# AudioAmplifier.net
KiCad netlist of a schematic drawn in Altium Designer
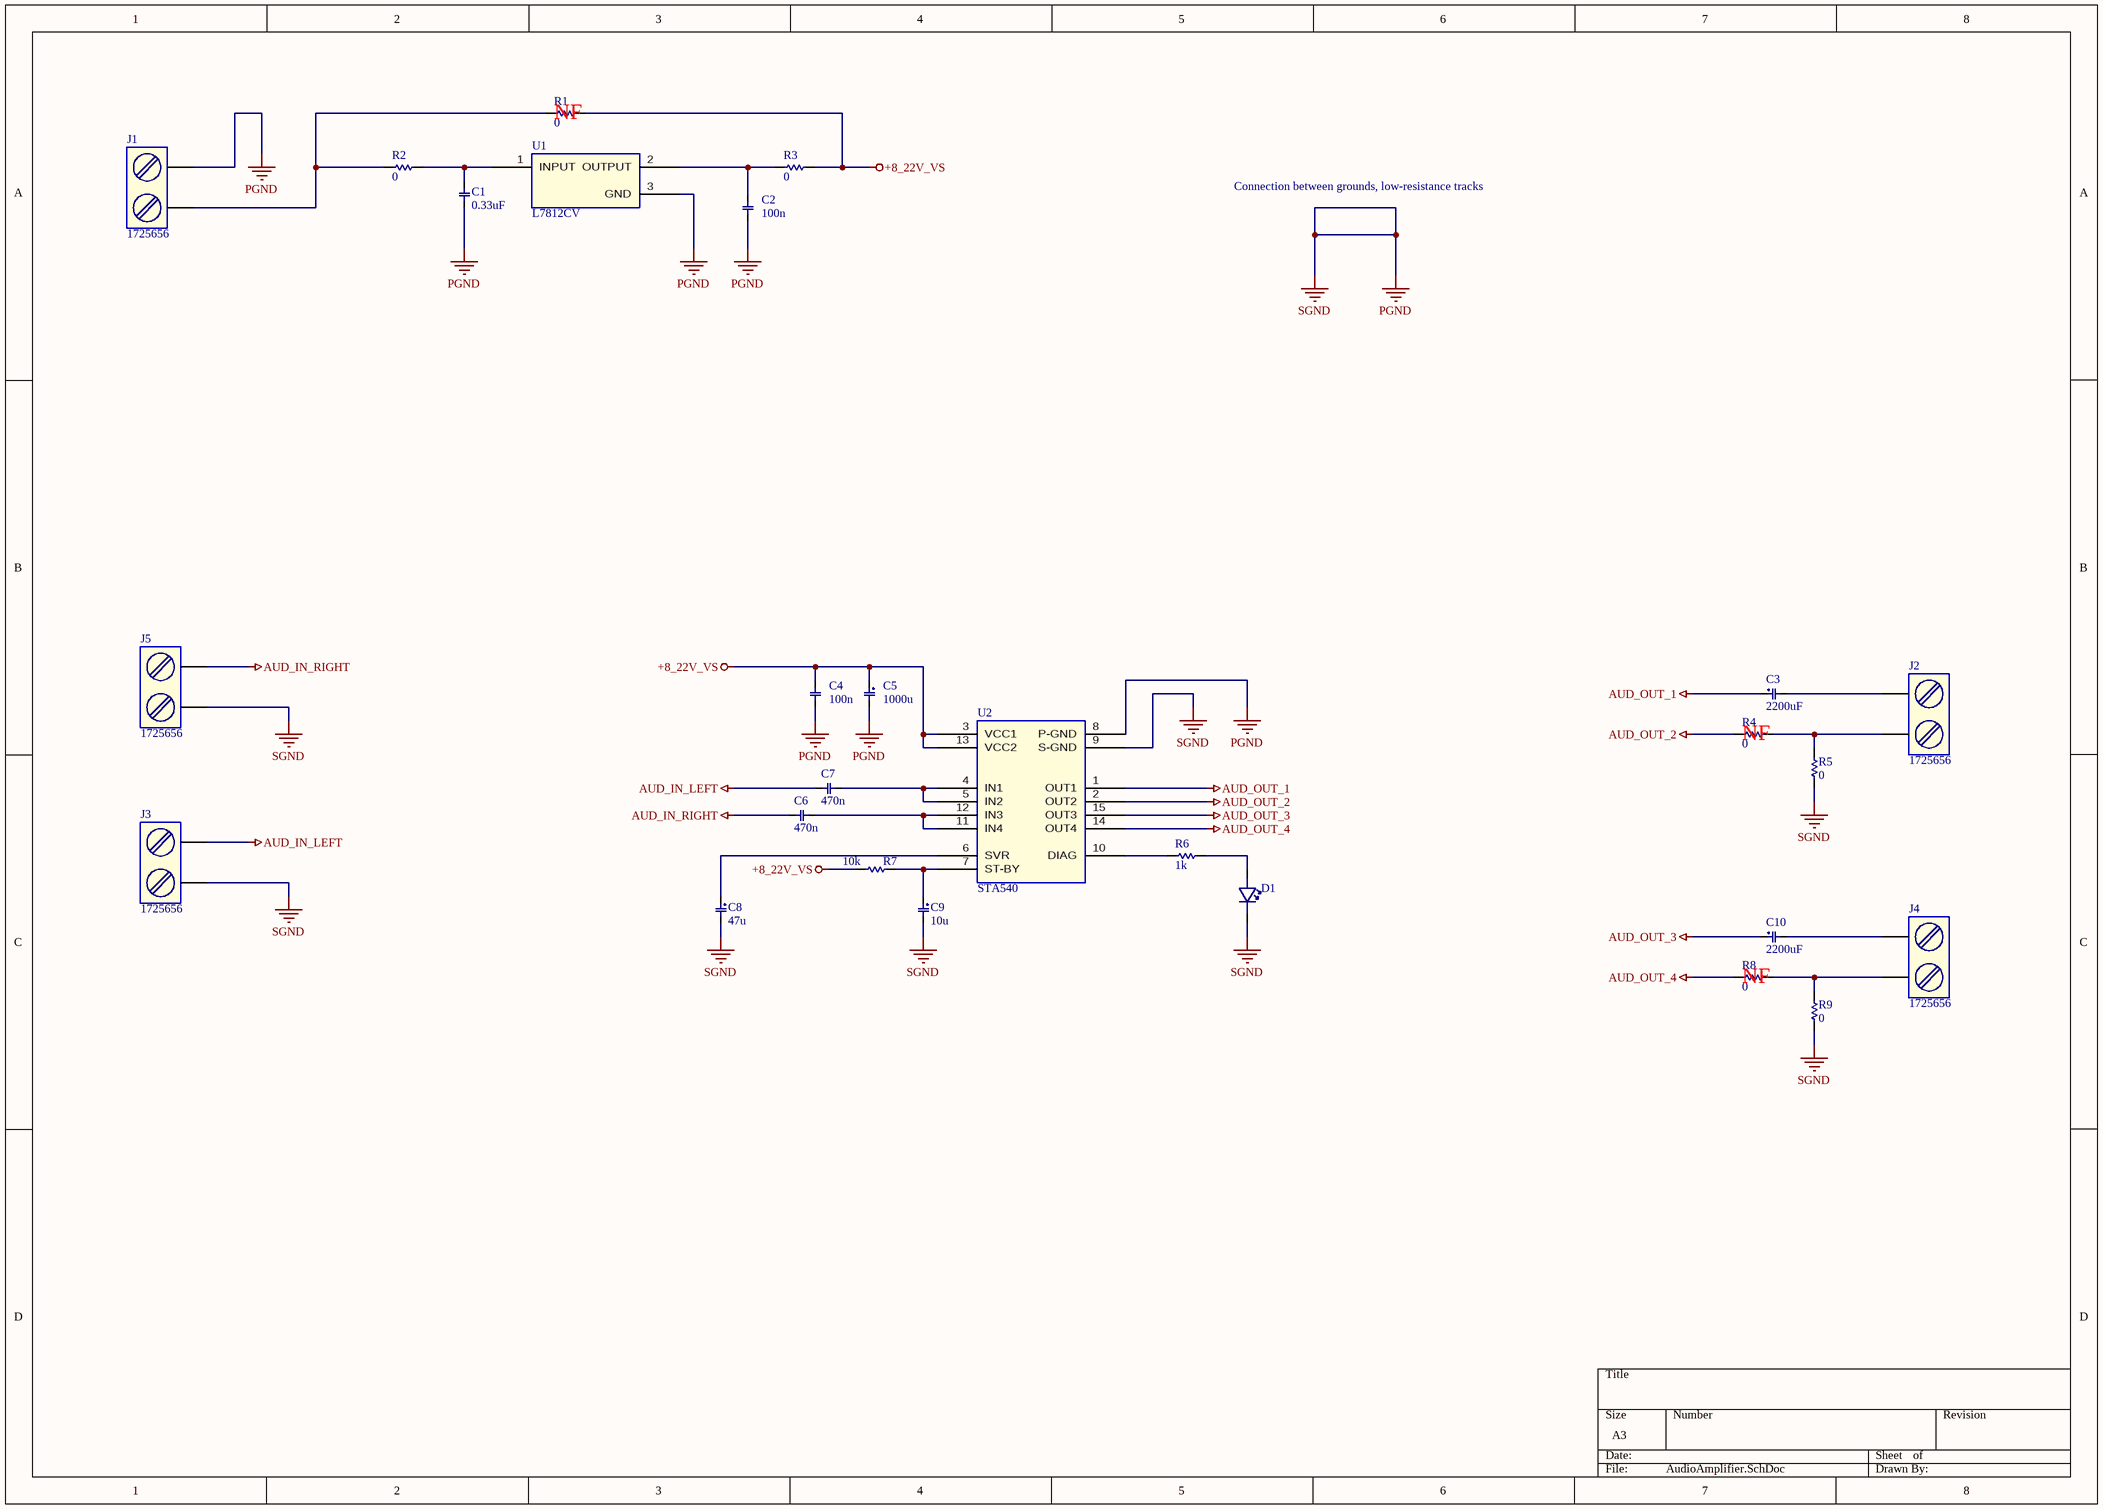
[diagram p0: AudioAmplifier.SchDoc]

(export (version "E")
  (design (tool "Eeschema 10.0.6"))
  (components
    (comp (ref "C1")
      (value "0.33uF")
      (footprint "CERAMIC CAPACITOR")
      (description "Multilayer Ceramic Capacitors MLCC - Leaded 50volts .33uF 20%")
      (fields (field (name "MANUFACTURER") "AVX") (field (name "MANUFACTURER PART NUMBER") "SR215E334MARTR2"))
      (libsource (lib "AudioAmplifier") (part "SR215E334MARTR2"))
    )
    (comp (ref "C2")
      (value "100n")
      (footprint "CERAMIC CAPACITOR")
      (description "Multilayer Ceramic Capacitors MLCC - Leaded .1uF 50volts 10% 5.0mm X7R")
      (fields
        (field (name "MANUFACTURER") "Vishay / BC Components")
        (field (name "MANUFACTURER PART NUMBER") "K104K15X7RF5UH5")
      )
      (libsource (lib "AudioAmplifier") (part "K104K15X7RF5UH5"))
    )
    (comp (ref "C3")
      (value "2200uF")
      (footprint "ELECTROLYTIC_CAPACITOR")
      (description "Aluminium Electrolytic Capacitors - Leaded 50volts 2200uF 16x31.5 20% 7.5LS")
      (fields
        (field (name "MANUFACTURER") "Nichicon")
        (field (name "MANUFACTURER PART NUMBER") "UVK1H222MHD")
      )
      (libsource (lib "AudioAmplifier") (part "UVK1H222MHD"))
    )
    (comp (ref "C4")
      (value "100n")
      (footprint "CERAMIC CAPACITOR")
      (description "Multilayer Ceramic Capacitors MLCC - Leaded .1uF 50volts 10% 5.0mm X7R")
      (fields
        (field (name "MANUFACTURER") "Vishay / BC Components")
        (field (name "MANUFACTURER PART NUMBER") "K104K15X7RF5UH5")
      )
      (libsource (lib "AudioAmplifier") (part "K104K15X7RF5UH5"))
    )
    (comp (ref "C5")
      (value "1000u")
      (footprint "ELECTROLYTIC_CAPACITOR")
      (description "Aluminium Electrolytic Capacitors - Leaded 1000uF 25V 85c")
      (fields
        (field (name "MANUFACTURER") "Nichicon")
        (field (name "MANUFACTURER PART NUMBER") "UVR1E102MPD1TD")
      )
      (libsource (lib "AudioAmplifier") (part "UVR1E102MPD1TD"))
    )
    (comp (ref "C6")
      (value "470n")
      (footprint "CERAMIC CAPACITOR")
      (description "Multilayer Ceramic Capacitors MLCC - Leaded 0.47uF 25volts X5R +/-10%")
      (fields (field (name "MANUFACTURER") "TDK") (field (name "MANUFACTURER PART NUMBER") "FK28X5R1E474K"))
      (libsource (lib "AudioAmplifier") (part "FK28X5R1E474K"))
    )
    (comp (ref "C7")
      (value "470n")
      (footprint "CERAMIC CAPACITOR")
      (description "Multilayer Ceramic Capacitors MLCC - Leaded 0.47uF 25volts X5R +/-10%")
      (fields (field (name "MANUFACTURER") "TDK") (field (name "MANUFACTURER PART NUMBER") "FK28X5R1E474K"))
      (libsource (lib "AudioAmplifier") (part "FK28X5R1E474K"))
    )
    (comp (ref "C8")
      (value "47u")
      (footprint "ELECTROLYTIC_CAPACITOR")
      (description "Aluminium Electrolytic Capacitors - Leaded 35V 47uF 105C 6.3x11mm")
      (fields
        (field (name "MANUFACTURER") "Lelon")
        (field (name "MANUFACTURER PART NUMBER") "RGA470M1VBK-0611G")
      )
      (libsource (lib "AudioAmplifier") (part "RGA470M1VBK-0611G"))
    )
    (comp (ref "C9")
      (value "10u")
      (footprint "ELECTROLYTIC_CAPACITOR")
      (description "Aluminium Electrolytic Capacitors - Leaded 50V 10uF 20% 5x11mm")
      (fields
        (field (name "MANUFACTURER") "Lelon")
        (field (name "MANUFACTURER PART NUMBER") "REA100M1HBK-0511P")
      )
      (libsource (lib "AudioAmplifier") (part "REA100M1HBK-0511P"))
    )
    (comp (ref "C10")
      (value "2200uF")
      (footprint "ELECTROLYTIC_CAPACITOR")
      (description "Aluminium Electrolytic Capacitors - Leaded 50volts 2200uF 16x31.5 20% 7.5LS")
      (fields
        (field (name "MANUFACTURER") "Nichicon")
        (field (name "MANUFACTURER PART NUMBER") "UVK1H222MHD")
      )
      (libsource (lib "AudioAmplifier") (part "UVK1H222MHD"))
    )
    (comp (ref "D1")
      (value "350-00006")
      (footprint "LED")
      (description "Standard LEDs - Through Hole Red LED")
      (fields (field (name "MANUFACTURER") "Parallax"))
      (libsource (lib "AudioAmplifier") (part "350-00006"))
    )
    (comp (ref "J1")
      (value "1725656")
      (footprint "1725656")
      (description "Fixed Terminal Blocks 2P 2.54mm 90DEG")
      (fields (field (name "MANUFACTURER") "Phoenix Contact"))
      (libsource (lib "") (part "1725656_1"))
    )
    (comp (ref "J2")
      (value "1725656")
      (footprint "1725656")
      (description "Fixed Terminal Blocks 2P 2.54mm 90DEG")
      (fields (field (name "MANUFACTURER") "Phoenix Contact"))
      (libsource (lib "AudioAmplifier") (part "1725656"))
    )
    (comp (ref "J3")
      (value "1725656")
      (footprint "1725656")
      (description "Fixed Terminal Blocks 2P 2.54mm 90DEG")
      (fields (field (name "MANUFACTURER") "Phoenix Contact"))
      (libsource (lib "") (part "1725656_1"))
    )
    (comp (ref "J4")
      (value "1725656")
      (footprint "1725656")
      (description "Fixed Terminal Blocks 2P 2.54mm 90DEG")
      (fields (field (name "MANUFACTURER") "Phoenix Contact"))
      (libsource (lib "AudioAmplifier") (part "1725656"))
    )
    (comp (ref "J5")
      (value "1725656")
      (footprint "1725656")
      (description "Fixed Terminal Blocks 2P 2.54mm 90DEG")
      (fields (field (name "MANUFACTURER") "Phoenix Contact"))
      (libsource (lib "") (part "1725656_1"))
    )
    (comp (ref "R1")
      (value "0")
      (footprint "Resistor")
      (description "Metal Film Resistors - Through Hole 400mW 0 Ohm Jumper SFR55 Historical p/n")
      (fields
        (field (name "MANUFACTURER") "Vishay / BC Components")
        (field (name "MANUFACTURER PART NUMBER") "SFR25000Z0000ZR500")
      )
      (libsource (lib "AudioAmplifier") (part "SFR25000Z0000ZR500"))
    )
    (comp (ref "R2")
      (value "0")
      (footprint "Resistor")
      (description "Metal Film Resistors - Through Hole 400mW 0 Ohm Jumper SFR55 Historical p/n")
      (fields
        (field (name "MANUFACTURER") "Vishay / BC Components")
        (field (name "MANUFACTURER PART NUMBER") "SFR25000Z0000ZR500")
      )
      (libsource (lib "AudioAmplifier") (part "SFR25000Z0000ZR500"))
    )
    (comp (ref "R3")
      (value "0")
      (footprint "Resistor")
      (description "Metal Film Resistors - Through Hole 400mW 0 Ohm Jumper SFR55 Historical p/n")
      (fields
        (field (name "MANUFACTURER") "Vishay / BC Components")
        (field (name "MANUFACTURER PART NUMBER") "SFR25000Z0000ZR500")
      )
      (libsource (lib "AudioAmplifier") (part "SFR25000Z0000ZR500"))
    )
    (comp (ref "R4")
      (value "0")
      (footprint "Resistor")
      (description "Metal Film Resistors - Through Hole 400mW 0 Ohm Jumper SFR55 Historical p/n")
      (fields
        (field (name "MANUFACTURER") "Vishay / BC Components")
        (field (name "MANUFACTURER PART NUMBER") "SFR25000Z0000ZR500")
      )
      (libsource (lib "AudioAmplifier") (part "SFR25000Z0000ZR500"))
    )
    (comp (ref "R5")
      (value "0")
      (footprint "Resistor")
      (description "Metal Film Resistors - Through Hole 400mW 0 Ohm Jumper SFR55 Historical p/n")
      (fields
        (field (name "MANUFACTURER") "Vishay / BC Components")
        (field (name "MANUFACTURER PART NUMBER") "SFR25000Z0000ZR500")
      )
      (libsource (lib "AudioAmplifier") (part "SFR25000Z0000ZR500"))
    )
    (comp (ref "R6")
      (value "1k")
      (footprint "Resistor")
      (description "Metal Film Resistors - Through Hole 1/2W1K ohm 1%")
      (fields
        (field (name "MANUFACTURER") "KOA Speer")
        (field (name "MANUFACTURER PART NUMBER") "MFS1/2DCT52R1001F")
      )
      (libsource (lib "AudioAmplifier") (part "MFS1/2DCT52R1001F"))
    )
    (comp (ref "R7")
      (value "10k")
      (footprint "Resistor")
      (description "Metal Film Resistors - Through Hole 1/2watt 10Kohms 1%")
      (fields
        (field (name "MANUFACTURER") "Vishay / BC Components")
        (field (name "MANUFACTURER PART NUMBER") "SFR16S0001002FR500")
      )
      (libsource (lib "AudioAmplifier") (part "SFR16S0001002FR500"))
    )
    (comp (ref "R8")
      (value "0")
      (footprint "Resistor")
      (description "Metal Film Resistors - Through Hole 400mW 0 Ohm Jumper SFR55 Historical p/n")
      (fields
        (field (name "MANUFACTURER") "Vishay / BC Components")
        (field (name "MANUFACTURER PART NUMBER") "SFR25000Z0000ZR500")
      )
      (libsource (lib "AudioAmplifier") (part "SFR25000Z0000ZR500"))
    )
    (comp (ref "R9")
      (value "0")
      (footprint "Resistor")
      (description "Metal Film Resistors - Through Hole 400mW 0 Ohm Jumper SFR55 Historical p/n")
      (fields
        (field (name "MANUFACTURER") "Vishay / BC Components")
        (field (name "MANUFACTURER PART NUMBER") "SFR25000Z0000ZR500")
      )
      (libsource (lib "AudioAmplifier") (part "SFR25000Z0000ZR500"))
    )
    (comp (ref "U1")
      (value "L7812CV")
      (footprint "TO-220")
      (description "Linear Voltage Regulators 12V 1.5A Positive")
      (fields (field (name "MANUFACTURER") "STMicroelectronics"))
      (libsource (lib "AudioAmplifier") (part "L7812CV"))
    )
    (comp (ref "U2")
      (value "STA540")
      (footprint "Multiwatt15")
      (description "Audio Amplifiers 4-CH AB Audio AMP 4 X 13 W Dual/Quad")
      (fields (field (name "MANUFACTURER") "STMicroelectronics"))
      (libsource (lib "AudioAmplifier") (part "STA540"))
    )
  )
  (nets
    (net (code "1") (name "+8_22V_VS") (class "Default")
      (node (ref "C4") (pin "1") (pinfunction "1_1") (pintype "passive"))
      (node (ref "C5") (pin "1") (pinfunction "1_1") (pintype "passive"))
      (node (ref "R1") (pin "2") (pinfunction "2_2") (pintype "passive"))
      (node (ref "R3") (pin "2") (pinfunction "2_2") (pintype "passive"))
      (node (ref "R7") (pin "1") (pinfunction "1_1") (pintype "passive"))
      (node (ref "U2") (pin "13") (pinfunction "VCC2_13") (pintype "passive"))
      (node (ref "U2") (pin "3") (pinfunction "VCC1_3") (pintype "passive"))
    )
    (net (code "2") (name "AUD_IN_LEFT") (class "Default")
      (node (ref "C7") (pin "1") (pinfunction "1_1") (pintype "passive"))
      (node (ref "J3") (pin "2") (pinfunction "2_2") (pintype "passive"))
    )
    (net (code "3") (name "AUD_IN_RIGHT") (class "Default")
      (node (ref "C6") (pin "1") (pinfunction "1_1") (pintype "passive"))
      (node (ref "J5") (pin "2") (pinfunction "2_2") (pintype "passive"))
    )
    (net (code "4") (name "AUD_OUT_1") (class "Default")
      (node (ref "C3") (pin "1") (pinfunction "1_1") (pintype "passive"))
      (node (ref "U2") (pin "1") (pinfunction "OUT1_1") (pintype "passive"))
    )
    (net (code "5") (name "AUD_OUT_2") (class "Default")
      (node (ref "R4") (pin "1") (pinfunction "1_1") (pintype "passive"))
      (node (ref "U2") (pin "2") (pinfunction "OUT2_2") (pintype "passive"))
    )
    (net (code "6") (name "AUD_OUT_3") (class "Default")
      (node (ref "C10") (pin "1") (pinfunction "1_1") (pintype "passive"))
      (node (ref "U2") (pin "15") (pinfunction "OUT3_15") (pintype "passive"))
    )
    (net (code "7") (name "AUD_OUT_4") (class "Default")
      (node (ref "R8") (pin "1") (pinfunction "1_1") (pintype "passive"))
      (node (ref "U2") (pin "14") (pinfunction "OUT4_14") (pintype "passive"))
    )
    (net (code "8") (name "Net-(C3-Pad2)") (class "Default")
      (node (ref "C3") (pin "2") (pinfunction "2_2") (pintype "passive"))
      (node (ref "J2") (pin "1") (pinfunction "1_1") (pintype "passive"))
    )
    (net (code "9") (name "Net-(C10-Pad2)") (class "Default")
      (node (ref "C10") (pin "2") (pinfunction "2_2") (pintype "passive"))
      (node (ref "J4") (pin "1") (pinfunction "1_1") (pintype "passive"))
    )
    (net (code "10") (name "Net-(D1-Pad1)") (class "Default")
      (node (ref "D1") (pin "1") (pinfunction "1_1") (pintype "passive"))
      (node (ref "R6") (pin "1") (pinfunction "1_1") (pintype "passive"))
    )
    (net (code "11") (name "Net-(J1-Pad1)") (class "Default")
      (node (ref "J1") (pin "1") (pinfunction "1_1") (pintype "passive"))
      (node (ref "R1") (pin "1") (pinfunction "1_1") (pintype "passive"))
      (node (ref "R2") (pin "1") (pinfunction "1_1") (pintype "passive"))
    )
    (net (code "12") (name "Net-(J2-Pad2)") (class "Default")
      (node (ref "J2") (pin "2") (pinfunction "2_2") (pintype "passive"))
      (node (ref "R4") (pin "2") (pinfunction "2_2") (pintype "passive"))
      (node (ref "R5") (pin "2") (pinfunction "2_2") (pintype "passive"))
    )
    (net (code "13") (name "Net-(J4-Pad2)") (class "Default")
      (node (ref "J4") (pin "2") (pinfunction "2_2") (pintype "passive"))
      (node (ref "R8") (pin "2") (pinfunction "2_2") (pintype "passive"))
      (node (ref "R9") (pin "2") (pinfunction "2_2") (pintype "passive"))
    )
    (net (code "14") (name "Net-(U1-INPUT)") (class "Default")
      (node (ref "C1") (pin "2") (pinfunction "2_2") (pintype "passive"))
      (node (ref "R2") (pin "2") (pinfunction "2_2") (pintype "passive"))
      (node (ref "U1") (pin "1") (pinfunction "INPUT_1") (pintype "passive"))
    )
    (net (code "15") (name "Net-(U1-OUTPUT)") (class "Default")
      (node (ref "C2") (pin "1") (pinfunction "1_1") (pintype "passive"))
      (node (ref "R3") (pin "1") (pinfunction "1_1") (pintype "passive"))
      (node (ref "U1") (pin "2") (pinfunction "OUTPUT_2") (pintype "passive"))
    )
    (net (code "16") (name "Net-(U2-DIAG)") (class "Default")
      (node (ref "R6") (pin "2") (pinfunction "2_2") (pintype "passive"))
      (node (ref "U2") (pin "10") (pinfunction "DIAG_10") (pintype "passive"))
    )
    (net (code "17") (name "Net-(U2-IN1)") (class "Default")
      (node (ref "C7") (pin "2") (pinfunction "2_2") (pintype "passive"))
      (node (ref "U2") (pin "4") (pinfunction "IN1_4") (pintype "passive"))
      (node (ref "U2") (pin "5") (pinfunction "IN2_5") (pintype "passive"))
    )
    (net (code "18") (name "Net-(U2-IN3)") (class "Default")
      (node (ref "C6") (pin "2") (pinfunction "2_2") (pintype "passive"))
      (node (ref "U2") (pin "11") (pinfunction "IN4_11") (pintype "passive"))
      (node (ref "U2") (pin "12") (pinfunction "IN3_12") (pintype "passive"))
    )
    (net (code "19") (name "Net-(U2-ST-BY)") (class "Default")
      (node (ref "C9") (pin "1") (pinfunction "1_1") (pintype "passive"))
      (node (ref "R7") (pin "2") (pinfunction "2_2") (pintype "passive"))
      (node (ref "U2") (pin "7") (pinfunction "ST-BY_7") (pintype "passive"))
    )
    (net (code "20") (name "Net-(U2-SVR)") (class "Default")
      (node (ref "C8") (pin "1") (pinfunction "1_1") (pintype "passive"))
      (node (ref "U2") (pin "6") (pinfunction "SVR_6") (pintype "passive"))
    )
    (net (code "21") (name "PGND") (class "Default")
      (node (ref "C1") (pin "1") (pinfunction "1_1") (pintype "passive"))
      (node (ref "C2") (pin "2") (pinfunction "2_2") (pintype "passive"))
      (node (ref "C4") (pin "2") (pinfunction "2_2") (pintype "passive"))
      (node (ref "C5") (pin "2") (pinfunction "2_2") (pintype "passive"))
      (node (ref "C8") (pin "2") (pinfunction "2_2") (pintype "passive"))
      (node (ref "C9") (pin "2") (pinfunction "2_2") (pintype "passive"))
      (node (ref "D1") (pin "2") (pinfunction "2_2") (pintype "passive"))
      (node (ref "J1") (pin "2") (pinfunction "2_2") (pintype "passive"))
      (node (ref "J3") (pin "1") (pinfunction "1_1") (pintype "passive"))
      (node (ref "J5") (pin "1") (pinfunction "1_1") (pintype "passive"))
      (node (ref "R5") (pin "1") (pinfunction "1_1") (pintype "passive"))
      (node (ref "R9") (pin "1") (pinfunction "1_1") (pintype "passive"))
      (node (ref "U1") (pin "3") (pinfunction "GND_3") (pintype "passive"))
      (node (ref "U2") (pin "8") (pinfunction "P-GND_8") (pintype "passive"))
      (node (ref "U2") (pin "9") (pinfunction "S-GND_9") (pintype "passive"))
    )
  )
)
